# PCB_OnOnfre_DUAL_5A_beta2.net
KiCad netlist of a schematic drawn in EAGLE
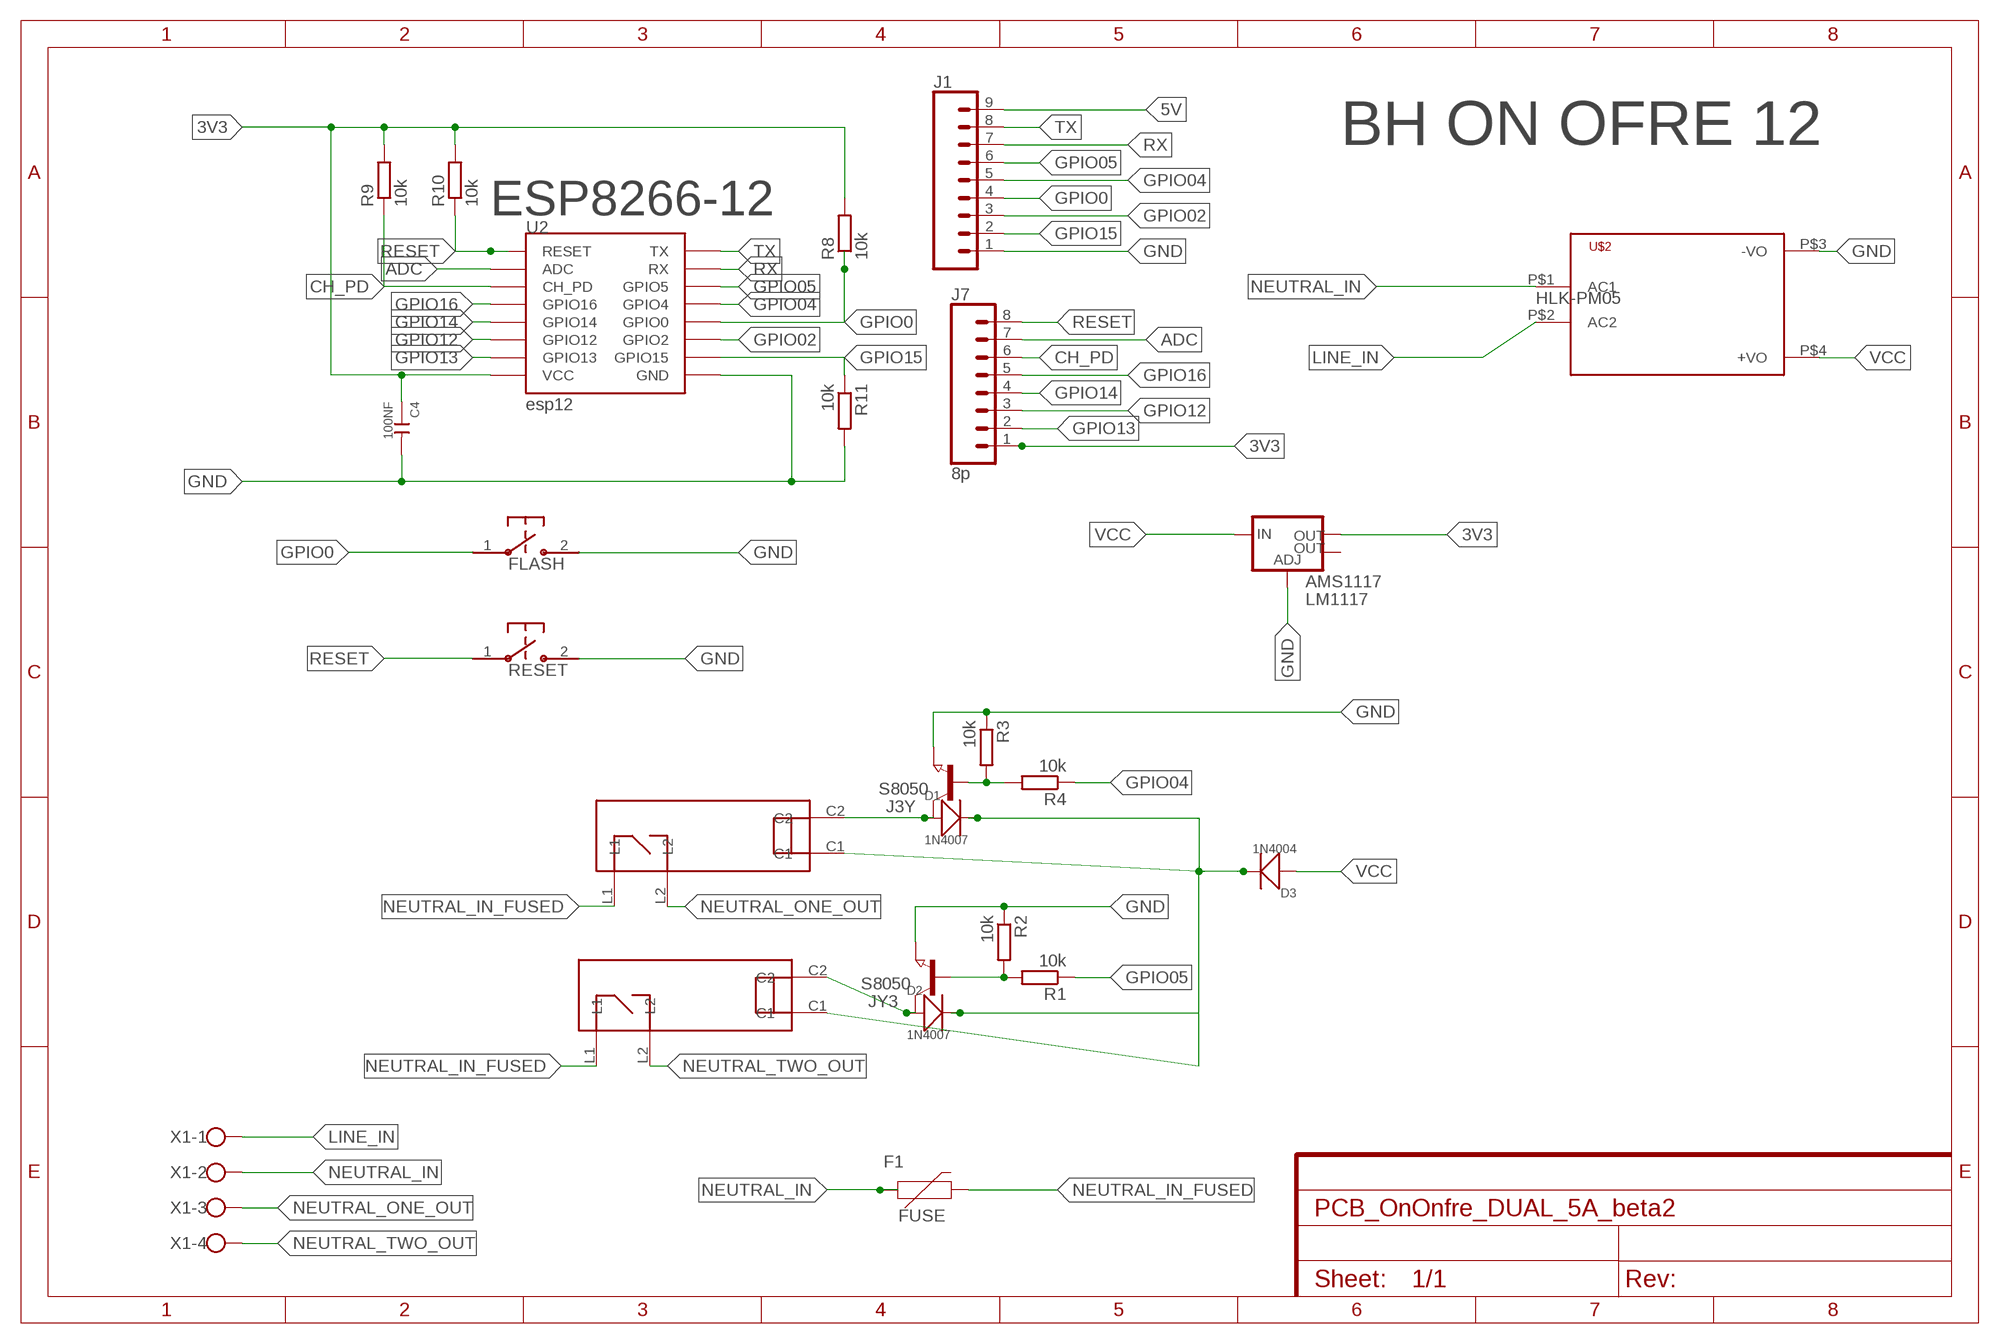
[diagram p0: schematic, sheet 1]

(export (version "E")
  (design (tool "Eeschema 10.0.6"))
  (components
    (comp (ref "AMS1117")
      (value "LM1117")
      (footprint "eagle-import:SOT223")
      (libsource (lib "eagle-import") (part "V_REG_LM1117SOT223"))
    )
    (comp (ref "C4")
      (value "100NF")
      (footprint "eagle-import:C1206")
      (fields (field (name "MPN") "CC1206KKX7RCBB102"))
      (libsource (lib "eagle-import") (part "CERAMIC-1NF-1KV-10%-X7R?(1206)"))
    )
    (comp (ref "D1")
      (value "1N4007")
      (footprint "eagle-import:DO-214AC")
      (libsource (lib "eagle-import") (part "DIODE-GEN-PURPOSE-1KV-1A(DO-214AC)"))
    )
    (comp (ref "D2")
      (value "1N4007")
      (footprint "eagle-import:DO-214AC")
      (libsource (lib "eagle-import") (part "DIODE-GEN-PURPOSE-1KV-1A(DO-214AC)"))
    )
    (comp (ref "D3")
      (value "1N4004")
      (footprint "eagle-import:DO-214AC")
      (fields (field (name "MPN") "1N4007"))
      (libsource (lib "eagle-import") (part "DIODE-GEN-PURPOSE-1KV-1A(DO-214AC)"))
    )
    (comp (ref "F1")
      (value "FUSE")
      (footprint "eagle-import:PTH")
      (libsource (lib "eagle-import") (part "PPTC_PTH"))
    )
    (comp (ref "FLASH")
      (value "B3U-1000P-2P-SMD")
      (footprint "eagle-import:B3U-1000P")
      (fields (field (name "MANUFACTURER") "Omron") (field (name "MPN") "B3U-1000P"))
      (libsource (lib "eagle-import") (part "B3U-1000P"))
    )
    (comp (ref "J1")
      (value "CONN_09")
      (footprint "eagle-import:1X09")
      (libsource (lib "eagle-import") (part "CONN_09"))
    )
    (comp (ref "J3Y")
      (value "S8050")
      (footprint "eagle-import:SOT23")
      (libsource (lib "eagle-import") (part "NPN-TRANSISTOR_SOT23"))
    )
    (comp (ref "J7")
      (value "8p")
      (footprint "eagle-import:1X08")
      (libsource (lib "eagle-import") (part "CONN_08{dblquote}"))
    )
    (comp (ref "JY3")
      (value "S8050")
      (footprint "eagle-import:SOT23")
      (libsource (lib "eagle-import") (part "NPN-TRANSISTOR_SOT23"))
    )
    (comp (ref "R1")
      (value "10k")
      (footprint "eagle-import:R0603")
      (libsource (lib "eagle-import") (part "R-EU_R0603"))
    )
    (comp (ref "R2")
      (value "10k")
      (footprint "eagle-import:R0603")
      (libsource (lib "eagle-import") (part "R-EU_R0603"))
    )
    (comp (ref "R3")
      (value "10k")
      (footprint "eagle-import:R0603")
      (libsource (lib "eagle-import") (part "R-EU_R0603"))
    )
    (comp (ref "R4")
      (value "10k")
      (footprint "eagle-import:R0603")
      (libsource (lib "eagle-import") (part "R-EU_R0603"))
    )
    (comp (ref "R8")
      (value "10k")
      (footprint "eagle-import:R0603")
      (libsource (lib "eagle-import") (part "R-EU_R0603"))
    )
    (comp (ref "R9")
      (value "10k")
      (footprint "eagle-import:R0603")
      (libsource (lib "eagle-import") (part "R-EU_R0603"))
    )
    (comp (ref "R10")
      (value "10k")
      (footprint "eagle-import:R0603")
      (libsource (lib "eagle-import") (part "R-EU_R0603"))
    )
    (comp (ref "R11")
      (value "10k")
      (footprint "eagle-import:R0603")
      (libsource (lib "eagle-import") (part "R-EU_R0603"))
    )
    (comp (ref "RESET")
      (value "B3U-1000P-2P-SMD")
      (footprint "eagle-import:B3U-1000P")
      (fields (field (name "MANUFACTURER") "Omron") (field (name "MPN") "B3U-1000P"))
      (libsource (lib "eagle-import") (part "B3U-1000P"))
    )
    (comp (ref "U$1")
      (value "HF46F")
      (footprint "eagle-import:HF46F")
      (libsource (lib "eagle-import") (part "HF46F"))
    )
    (comp (ref "U$2")
      (value "HKLPM01")
      (footprint "eagle-import:HKLPM01")
      (libsource (lib "eagle-import") (part "HKLPM01"))
    )
    (comp (ref "U$3")
      (value "HF46F")
      (footprint "eagle-import:HF46F")
      (libsource (lib "eagle-import") (part "HF46F"))
    )
    (comp (ref "U2")
      (value "esp12")
      (footprint "eagle-import:ESP12-SMD")
      (libsource (lib "eagle-import") (part "ESP12SMD"))
    )
    (comp (ref "X1")
      (value "W237-4")
      (footprint "eagle-import:W237-4")
      (libsource (lib "eagle-import") (part "W237-4"))
    )
  )
  (nets
    (net (code "1") (name "3V3") (class "Default")
      (node (ref "AMS1117") (pin "2") (pinfunction "OUT_2") (pintype "output"))
      (node (ref "C4") (pin "1") (pinfunction "1_1") (pintype "passive"))
      (node (ref "J7") (pin "1") (pinfunction "1_1") (pintype "passive"))
      (node (ref "R10") (pin "2") (pinfunction "2_2") (pintype "passive"))
      (node (ref "R8") (pin "2") (pinfunction "2_2") (pintype "passive"))
      (node (ref "R9") (pin "2") (pinfunction "2_2") (pintype "passive"))
      (node (ref "U2") (pin "VCC") (pinfunction "VCC_VCC") (pintype "bidirectional"))
    )
    (net (code "2") (name "5V") (class "Default")
      (node (ref "D1") (pin "2") (pinfunction "-_2") (pintype "passive"))
      (node (ref "D2") (pin "2") (pinfunction "-_2") (pintype "passive"))
      (node (ref "D3") (pin "2") (pinfunction "-_2") (pintype "passive"))
      (node (ref "J1") (pin "9") (pinfunction "9_9") (pintype "passive"))
      (node (ref "U$1") (pin "C1") (pinfunction "C1_C1") (pintype "bidirectional"))
      (node (ref "U$3") (pin "C1") (pinfunction "C1_C1") (pintype "bidirectional"))
    )
    (net (code "3") (name "ADC") (class "Default")
      (node (ref "J7") (pin "7") (pinfunction "7_7") (pintype "passive"))
      (node (ref "U2") (pin "ADC") (pinfunction "ADC_ADC") (pintype "bidirectional"))
    )
    (net (code "4") (name "CH_PD") (class "Default")
      (node (ref "J7") (pin "6") (pinfunction "6_6") (pintype "passive"))
      (node (ref "R9") (pin "1") (pinfunction "1_1") (pintype "passive"))
      (node (ref "U2") (pin "CH_PD") (pinfunction "CH_PD_CH_PD") (pintype "bidirectional"))
    )
    (net (code "5") (name "GND") (class "Default")
      (node (ref "AMS1117") (pin "1") (pinfunction "ADJ_1") (pintype "input"))
      (node (ref "C4") (pin "2") (pinfunction "2_2") (pintype "passive"))
      (node (ref "FLASH") (pin "2") (pinfunction "P$2_2") (pintype "passive"))
      (node (ref "J1") (pin "1") (pinfunction "1_1") (pintype "passive"))
      (node (ref "J3Y") (pin "2") (pinfunction "E_2") (pintype "passive"))
      (node (ref "JY3") (pin "2") (pinfunction "E_2") (pintype "passive"))
      (node (ref "R11") (pin "2") (pinfunction "2_2") (pintype "passive"))
      (node (ref "R2") (pin "1") (pinfunction "1_1") (pintype "passive"))
      (node (ref "R3") (pin "1") (pinfunction "1_1") (pintype "passive"))
      (node (ref "RESET") (pin "2") (pinfunction "P$2_2") (pintype "passive"))
      (node (ref "U$2") (pin "P$3") (pinfunction "-VO_P$3") (pintype "bidirectional"))
      (node (ref "U2") (pin "GND") (pinfunction "GND_GND") (pintype "bidirectional"))
    )
    (net (code "6") (name "GPIO0") (class "Default")
      (node (ref "FLASH") (pin "1") (pinfunction "P$1_1") (pintype "passive"))
      (node (ref "J1") (pin "4") (pinfunction "4_4") (pintype "passive"))
      (node (ref "R8") (pin "1") (pinfunction "1_1") (pintype "passive"))
      (node (ref "U2") (pin "GPIO0") (pinfunction "GPIO0_GPIO0") (pintype "bidirectional"))
    )
    (net (code "7") (name "GPIO02") (class "Default")
      (node (ref "J1") (pin "3") (pinfunction "3_3") (pintype "passive"))
      (node (ref "U2") (pin "GPIO2") (pinfunction "GPIO2_GPIO2") (pintype "bidirectional"))
    )
    (net (code "8") (name "GPIO04") (class "Default")
      (node (ref "J1") (pin "5") (pinfunction "5_5") (pintype "passive"))
      (node (ref "R4") (pin "1") (pinfunction "1_1") (pintype "passive"))
      (node (ref "U2") (pin "GPIO4") (pinfunction "GPIO4_GPIO4") (pintype "bidirectional"))
    )
    (net (code "9") (name "GPIO05") (class "Default")
      (node (ref "J1") (pin "6") (pinfunction "6_6") (pintype "passive"))
      (node (ref "R1") (pin "1") (pinfunction "1_1") (pintype "passive"))
      (node (ref "U2") (pin "GPIO5") (pinfunction "GPIO5_GPIO5") (pintype "bidirectional"))
    )
    (net (code "10") (name "GPIO12") (class "Default")
      (node (ref "J7") (pin "3") (pinfunction "3_3") (pintype "passive"))
      (node (ref "U2") (pin "GPIO12") (pinfunction "GPIO12_GPIO12") (pintype "bidirectional"))
    )
    (net (code "11") (name "GPIO13") (class "Default")
      (node (ref "J7") (pin "2") (pinfunction "2_2") (pintype "passive"))
      (node (ref "U2") (pin "GPIO13") (pinfunction "GPIO13_GPIO13") (pintype "bidirectional"))
    )
    (net (code "12") (name "GPIO14") (class "Default")
      (node (ref "J7") (pin "4") (pinfunction "4_4") (pintype "passive"))
      (node (ref "U2") (pin "GPIO14") (pinfunction "GPIO14_GPIO14") (pintype "bidirectional"))
    )
    (net (code "13") (name "GPIO15") (class "Default")
      (node (ref "J1") (pin "2") (pinfunction "2_2") (pintype "passive"))
      (node (ref "R11") (pin "1") (pinfunction "1_1") (pintype "passive"))
      (node (ref "U2") (pin "GPIO15") (pinfunction "GPIO15_GPIO15") (pintype "bidirectional"))
    )
    (net (code "14") (name "GPIO16") (class "Default")
      (node (ref "J7") (pin "5") (pinfunction "5_5") (pintype "passive"))
      (node (ref "U2") (pin "GPIO16") (pinfunction "GPIO16_GPIO16") (pintype "bidirectional"))
    )
    (net (code "15") (name "LINE_IN") (class "Default")
      (node (ref "U$2") (pin "P$2") (pinfunction "AC2_P$2") (pintype "bidirectional"))
      (node (ref "X1") (pin "1") (pinfunction "KL_1") (pintype "passive"))
    )
    (net (code "16") (name "NEUTRAL_IN") (class "Default")
      (node (ref "F1") (pin "P$1") (pinfunction "1_P$1") (pintype "bidirectional"))
      (node (ref "U$2") (pin "P$1") (pinfunction "AC1_P$1") (pintype "bidirectional"))
      (node (ref "X1") (pin "2") (pinfunction "KL_2") (pintype "passive"))
    )
    (net (code "17") (name "NEUTRAL_IN_FUSED") (class "Default")
      (node (ref "F1") (pin "P$2") (pinfunction "2_P$2") (pintype "bidirectional"))
      (node (ref "U$1") (pin "L1") (pinfunction "L1_L1") (pintype "bidirectional"))
      (node (ref "U$3") (pin "L1") (pinfunction "L1_L1") (pintype "bidirectional"))
    )
    (net (code "18") (name "NEUTRAL_ONE_OUT") (class "Default")
      (node (ref "U$1") (pin "L2") (pinfunction "L2_L2") (pintype "bidirectional"))
      (node (ref "X1") (pin "3") (pinfunction "KL_3") (pintype "passive"))
    )
    (net (code "19") (name "NEUTRAL_TWO_OUT") (class "Default")
      (node (ref "U$3") (pin "L2") (pinfunction "L2_L2") (pintype "bidirectional"))
      (node (ref "X1") (pin "4") (pinfunction "KL_4") (pintype "passive"))
    )
    (net (code "20") (name "Net-(D1-+)") (class "Default")
      (node (ref "D1") (pin "1") (pinfunction "+_1") (pintype "passive"))
      (node (ref "J3Y") (pin "3") (pinfunction "C_3") (pintype "passive"))
      (node (ref "U$1") (pin "C2") (pinfunction "C2_C2") (pintype "bidirectional"))
    )
    (net (code "21") (name "Net-(D2-+)") (class "Default")
      (node (ref "D2") (pin "1") (pinfunction "+_1") (pintype "passive"))
      (node (ref "JY3") (pin "3") (pinfunction "C_3") (pintype "passive"))
      (node (ref "U$3") (pin "C2") (pinfunction "C2_C2") (pintype "bidirectional"))
    )
    (net (code "22") (name "Net-(J3Y-B)") (class "Default")
      (node (ref "J3Y") (pin "1") (pinfunction "B_1") (pintype "passive"))
      (node (ref "R3") (pin "2") (pinfunction "2_2") (pintype "passive"))
      (node (ref "R4") (pin "2") (pinfunction "2_2") (pintype "passive"))
    )
    (net (code "23") (name "Net-(JY3-B)") (class "Default")
      (node (ref "JY3") (pin "1") (pinfunction "B_1") (pintype "passive"))
      (node (ref "R1") (pin "2") (pinfunction "2_2") (pintype "passive"))
      (node (ref "R2") (pin "2") (pinfunction "2_2") (pintype "passive"))
    )
    (net (code "24") (name "RESET") (class "Default")
      (node (ref "J7") (pin "8") (pinfunction "8_8") (pintype "passive"))
      (node (ref "R10") (pin "1") (pinfunction "1_1") (pintype "passive"))
      (node (ref "RESET") (pin "1") (pinfunction "P$1_1") (pintype "passive"))
      (node (ref "U2") (pin "RESET") (pinfunction "RESET_RESET") (pintype "bidirectional"))
    )
    (net (code "25") (name "RX") (class "Default")
      (node (ref "J1") (pin "7") (pinfunction "7_7") (pintype "passive"))
      (node (ref "U2") (pin "RXD0") (pinfunction "RX_RXD0") (pintype "bidirectional"))
    )
    (net (code "26") (name "TX") (class "Default")
      (node (ref "J1") (pin "8") (pinfunction "8_8") (pintype "passive"))
      (node (ref "U2") (pin "TXD0") (pinfunction "TX_TXD0") (pintype "bidirectional"))
    )
    (net (code "27") (name "VCC") (class "Default")
      (node (ref "AMS1117") (pin "3") (pinfunction "IN_3") (pintype "input"))
      (node (ref "D3") (pin "1") (pinfunction "+_1") (pintype "passive"))
      (node (ref "U$2") (pin "P$4") (pinfunction "+VO_P$4") (pintype "bidirectional"))
    )
    (net (code "28") (name "unconnected-(AMS1117-OUT-Pad4)") (class "Default")
      (node (ref "AMS1117") (pin "4") (pinfunction "OUT_4") (pintype "output"))
    )
  )
)
